# 1DD-17-test-board-mk-1_0.net
KiCad netlist of a schematic drawn in EAGLE
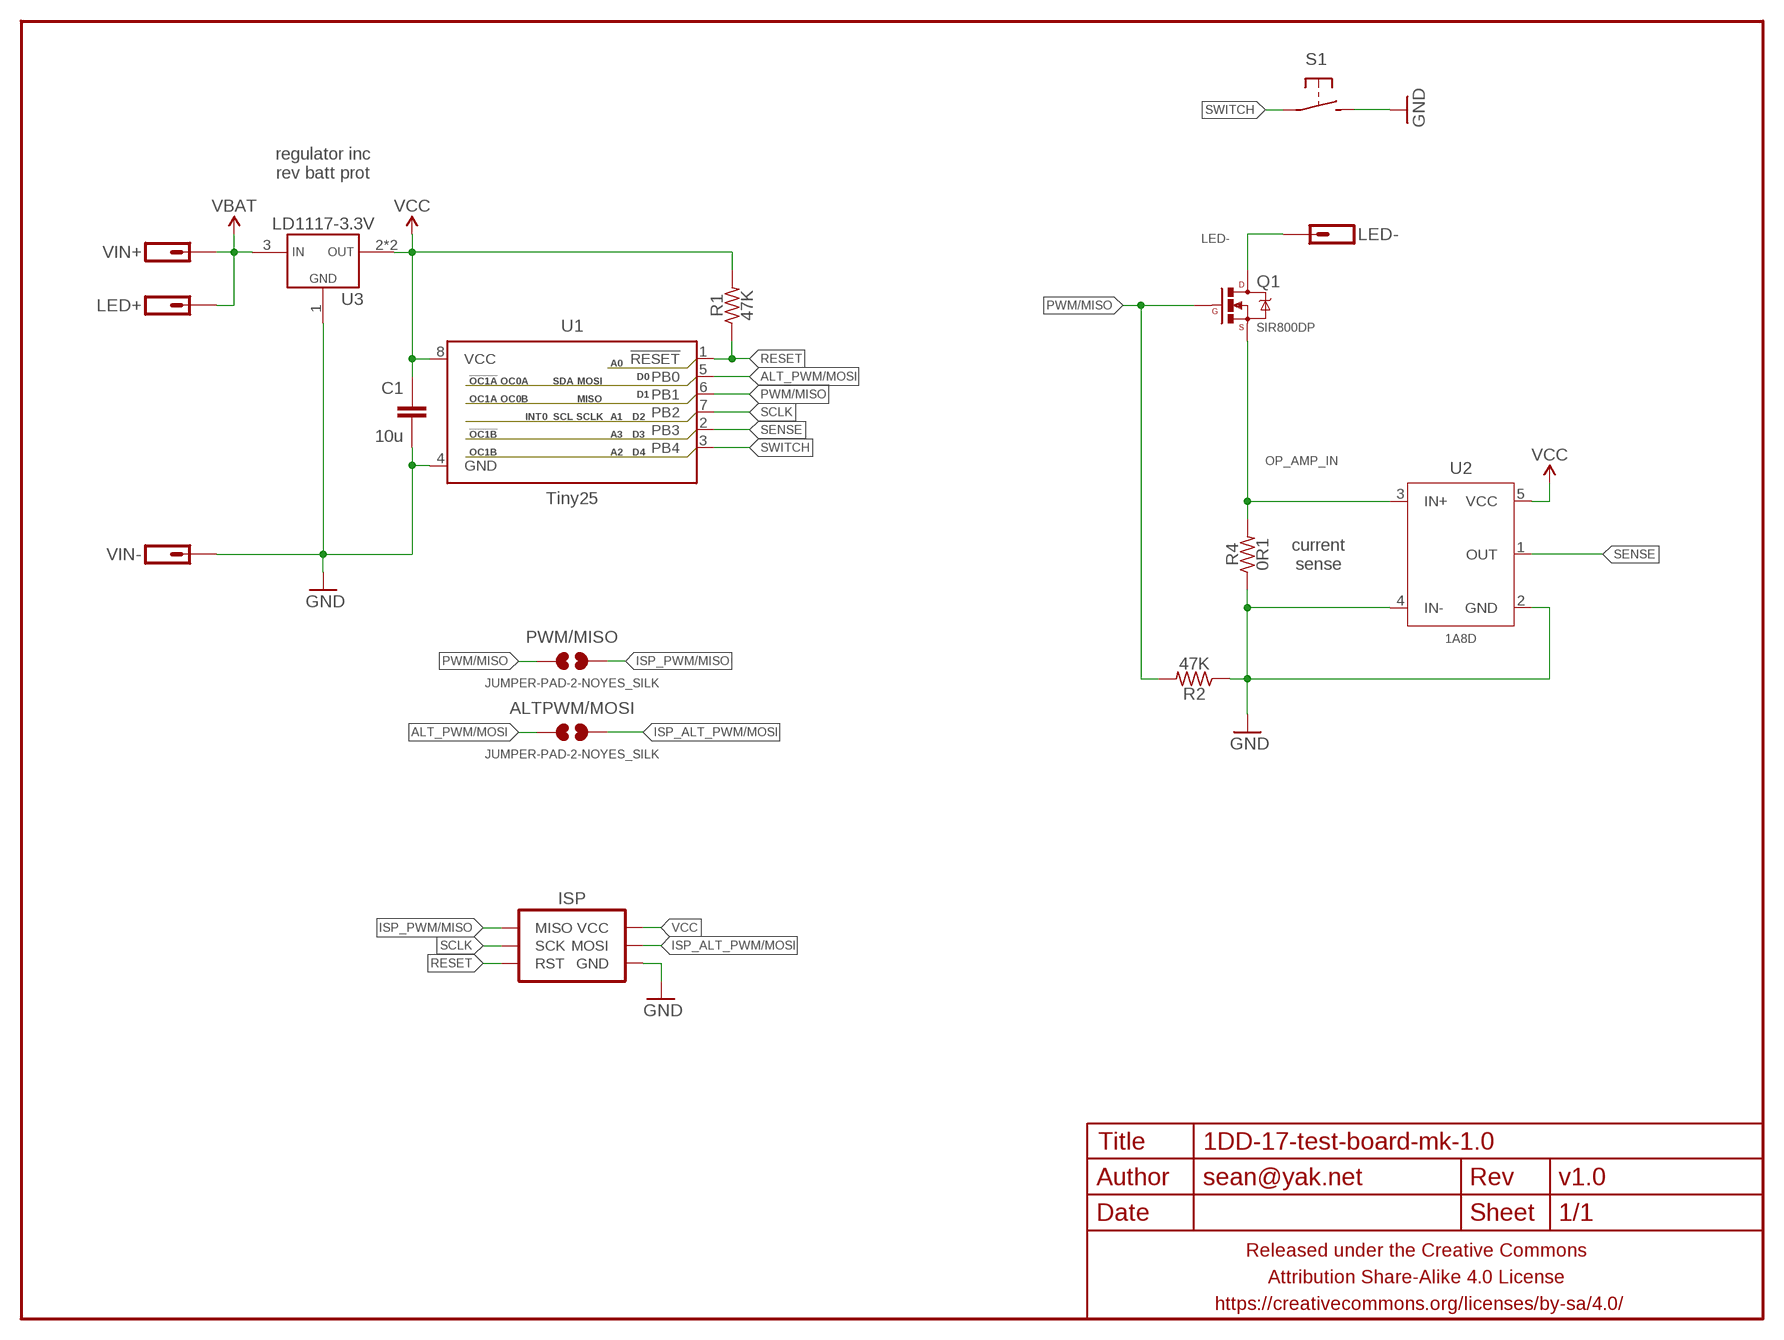
[diagram p0: schematic, sheet 1]

(export (version "E")
  (design (tool "Eeschema 10.0.6"))
  (components
    (comp (ref "ALTPWM/MOSI")
      (value "JUMPER-PAD-2-NOYES_SILK")
      (footprint "eagle-import:PAD-JUMPER-2-NO_YES_SILK")
      (libsource (lib "eagle-import") (part "JUMPER-PAD-2-NOYES_SILK"))
    )
    (comp (ref "C1")
      (value "10u")
      (footprint "eagle-import:C0805-TIGHTER")
      (libsource (lib "eagle-import") (part "CAPACITOR-CERAMICC0805-TIGHTER"))
    )
    (comp (ref "FRAME1")
      (value "FRAME-LETTERNO_PACKAGE")
      (footprint "eagle-import:DUMMY")
      (fields (field (name "DESIGNER") "sean@yak.net") (field (name "VERSION") "v1.0"))
      (libsource (lib "eagle-import") (part "FRAME-LETTERNO_PACKAGE"))
    )
    (comp (ref "ISP")
      (value "AVR_SPI_PRG_6PTH")
      (footprint "eagle-import:2X3")
      (libsource (lib "eagle-import") (part "AVR_SPI_PRG_6PTH"))
    )
    (comp (ref "LED+")
      (value "M01OFFSET")
      (footprint "eagle-import:1X01_OFFSET")
      (libsource (lib "eagle-import") (part "M01OFFSET"))
    )
    (comp (ref "LED-")
      (value "M01OFFSET")
      (footprint "eagle-import:1X01_OFFSET")
      (libsource (lib "eagle-import") (part "M01OFFSET"))
    )
    (comp (ref "PWM/MISO")
      (value "JUMPER-PAD-2-NOYES_SILK")
      (footprint "eagle-import:PAD-JUMPER-2-NO_YES_SILK")
      (libsource (lib "eagle-import") (part "JUMPER-PAD-2-NOYES_SILK"))
    )
    (comp (ref "Q1")
      (value "SIR800DP")
      (footprint "eagle-import:POWERPACK-SO-8")
      (libsource (lib "eagle-import") (part "MOSFET-NCHANNELSIR800DP"))
    )
    (comp (ref "R1")
      (value "47K")
      (footprint "eagle-import:R0603-TIGHTER")
      (libsource (lib "eagle-import") (part "RESISTORR0603-TIGHTER"))
    )
    (comp (ref "R2")
      (value "47K")
      (footprint "eagle-import:R0603-TIGHTER")
      (libsource (lib "eagle-import") (part "RESISTORR0603-TIGHTER"))
    )
    (comp (ref "R4")
      (value "0R1")
      (footprint "eagle-import:R1206")
      (libsource (lib "eagle-import") (part "RESISTORR1206"))
    )
    (comp (ref "S1")
      (value "SPST-NO-TACT3MM-PTH-SMALL-PADS")
      (footprint "eagle-import:DTS-3-SMALL-PADS")
      (libsource (lib "eagle-import") (part "SPST-NO-TACT3MM-PTH-SMALL-PADS"))
    )
    (comp (ref "U1")
      (value "Tiny25")
      (footprint "eagle-import:SO08-NARROWER")
      (libsource (lib "eagle-import") (part "ATTINY13SOIC-NARROWPADS"))
    )
    (comp (ref "U2")
      (value "1A8D")
      (footprint "eagle-import:SOT23-5-SLIM")
      (libsource (lib "eagle-import") (part "INA180DBV-ALT"))
    )
    (comp (ref "U3")
      (value "LD1117-3.3V")
      (footprint "eagle-import:SOT223")
      (libsource (lib "eagle-import") (part "VREG_1117SOT223"))
    )
    (comp (ref "VIN+")
      (value "M01OFFSET")
      (footprint "eagle-import:1X01_OFFSET")
      (libsource (lib "eagle-import") (part "M01OFFSET"))
    )
    (comp (ref "VIN-")
      (value "M01OFFSET")
      (footprint "eagle-import:1X01_OFFSET")
      (libsource (lib "eagle-import") (part "M01OFFSET"))
    )
  )
  (nets
    (net (code "1") (name "/LED-") (class "Default")
      (node (ref "LED-") (pin "1") (pinfunction "1_1") (pintype "passive"))
      (node (ref "Q1") (pin "5678") (pinfunction "D_5678") (pintype "passive"))
    )
    (net (code "2") (name "/OP_AMP_IN") (class "Default")
      (node (ref "Q1") (pin "1") (pinfunction "S_1") (pintype "passive"))
      (node (ref "Q1") (pin "2") (pinfunction "S_2") (pintype "passive"))
      (node (ref "Q1") (pin "3") (pinfunction "S_3") (pintype "passive"))
      (node (ref "R4") (pin "2") (pinfunction "2_2") (pintype "passive"))
      (node (ref "U2") (pin "3") (pinfunction "IN+_3") (pintype "bidirectional"))
    )
    (net (code "3") (name "ALT_PWM{slash}MOSI") (class "Default")
      (node (ref "ALTPWM/MOSI") (pin "1") (pinfunction "1_1") (pintype "passive"))
      (node (ref "U1") (pin "5") (pinfunction "PB0_5") (pintype "bidirectional"))
    )
    (net (code "4") (name "GND") (class "Default")
      (node (ref "C1") (pin "2") (pinfunction "2_2") (pintype "passive"))
      (node (ref "ISP") (pin "6") (pinfunction "GND_6") (pintype "passive"))
      (node (ref "R2") (pin "1") (pinfunction "1_1") (pintype "passive"))
      (node (ref "R4") (pin "1") (pinfunction "1_1") (pintype "passive"))
      (node (ref "S1") (pin "2") (pinfunction "2_2") (pintype "passive"))
      (node (ref "U1") (pin "4") (pinfunction "GND_4") (pintype "bidirectional"))
      (node (ref "U2") (pin "2") (pinfunction "GND_2") (pintype "bidirectional"))
      (node (ref "U2") (pin "4") (pinfunction "IN-_4") (pintype "bidirectional"))
      (node (ref "U3") (pin "1") (pinfunction "GND_1") (pintype "bidirectional"))
      (node (ref "VIN-") (pin "1") (pinfunction "1_1") (pintype "passive"))
    )
    (net (code "5") (name "ISP_ALT_PWM{slash}MOSI") (class "Default")
      (node (ref "ALTPWM/MOSI") (pin "2") (pinfunction "2_2") (pintype "passive"))
      (node (ref "ISP") (pin "4") (pinfunction "MOSI_4") (pintype "passive"))
    )
    (net (code "6") (name "ISP_PWM{slash}MISO") (class "Default")
      (node (ref "ISP") (pin "1") (pinfunction "MISO_1") (pintype "passive"))
      (node (ref "PWM/MISO") (pin "2") (pinfunction "2_2") (pintype "passive"))
    )
    (net (code "7") (name "PWM{slash}MISO") (class "Default")
      (node (ref "PWM/MISO") (pin "1") (pinfunction "1_1") (pintype "passive"))
      (node (ref "Q1") (pin "4") (pinfunction "G_4") (pintype "passive"))
      (node (ref "R2") (pin "2") (pinfunction "2_2") (pintype "passive"))
      (node (ref "U1") (pin "6") (pinfunction "PB1_6") (pintype "bidirectional"))
    )
    (net (code "8") (name "RESET") (class "Default")
      (node (ref "ISP") (pin "5") (pinfunction "RST_5") (pintype "passive"))
      (node (ref "R1") (pin "1") (pinfunction "1_1") (pintype "passive"))
      (node (ref "U1") (pin "1") (pinfunction "~{RESET}_1") (pintype "bidirectional"))
    )
    (net (code "9") (name "SCLK") (class "Default")
      (node (ref "ISP") (pin "3") (pinfunction "SCK_3") (pintype "passive"))
      (node (ref "U1") (pin "7") (pinfunction "PB2_7") (pintype "bidirectional"))
    )
    (net (code "10") (name "SENSE") (class "Default")
      (node (ref "U1") (pin "2") (pinfunction "PB3_2") (pintype "bidirectional"))
      (node (ref "U2") (pin "1") (pinfunction "OUT_1") (pintype "bidirectional"))
    )
    (net (code "11") (name "SWITCH") (class "Default")
      (node (ref "S1") (pin "1") (pinfunction "1_1") (pintype "passive"))
      (node (ref "U1") (pin "3") (pinfunction "PB4_3") (pintype "bidirectional"))
    )
    (net (code "12") (name "VBAT") (class "Default")
      (node (ref "LED+") (pin "1") (pinfunction "1_1") (pintype "passive"))
      (node (ref "U3") (pin "3") (pinfunction "VIN_3") (pintype "bidirectional"))
      (node (ref "VIN+") (pin "1") (pinfunction "1_1") (pintype "passive"))
    )
    (net (code "13") (name "VCC") (class "Default")
      (node (ref "C1") (pin "1") (pinfunction "1_1") (pintype "passive"))
      (node (ref "ISP") (pin "2") (pinfunction "VCC_2") (pintype "passive"))
      (node (ref "R1") (pin "2") (pinfunction "2_2") (pintype "passive"))
      (node (ref "U1") (pin "8") (pinfunction "VCC_8") (pintype "bidirectional"))
      (node (ref "U2") (pin "5") (pinfunction "VCC_5") (pintype "bidirectional"))
      (node (ref "U3") (pin "2") (pinfunction "VOUT_2") (pintype "bidirectional"))
      (node (ref "U3") (pin "4") (pinfunction "VOUT_4") (pintype "bidirectional"))
    )
  )
)
